# Adafruit_STEMMA_Soil_Sensor.net
KiCad netlist of a schematic drawn in EAGLE
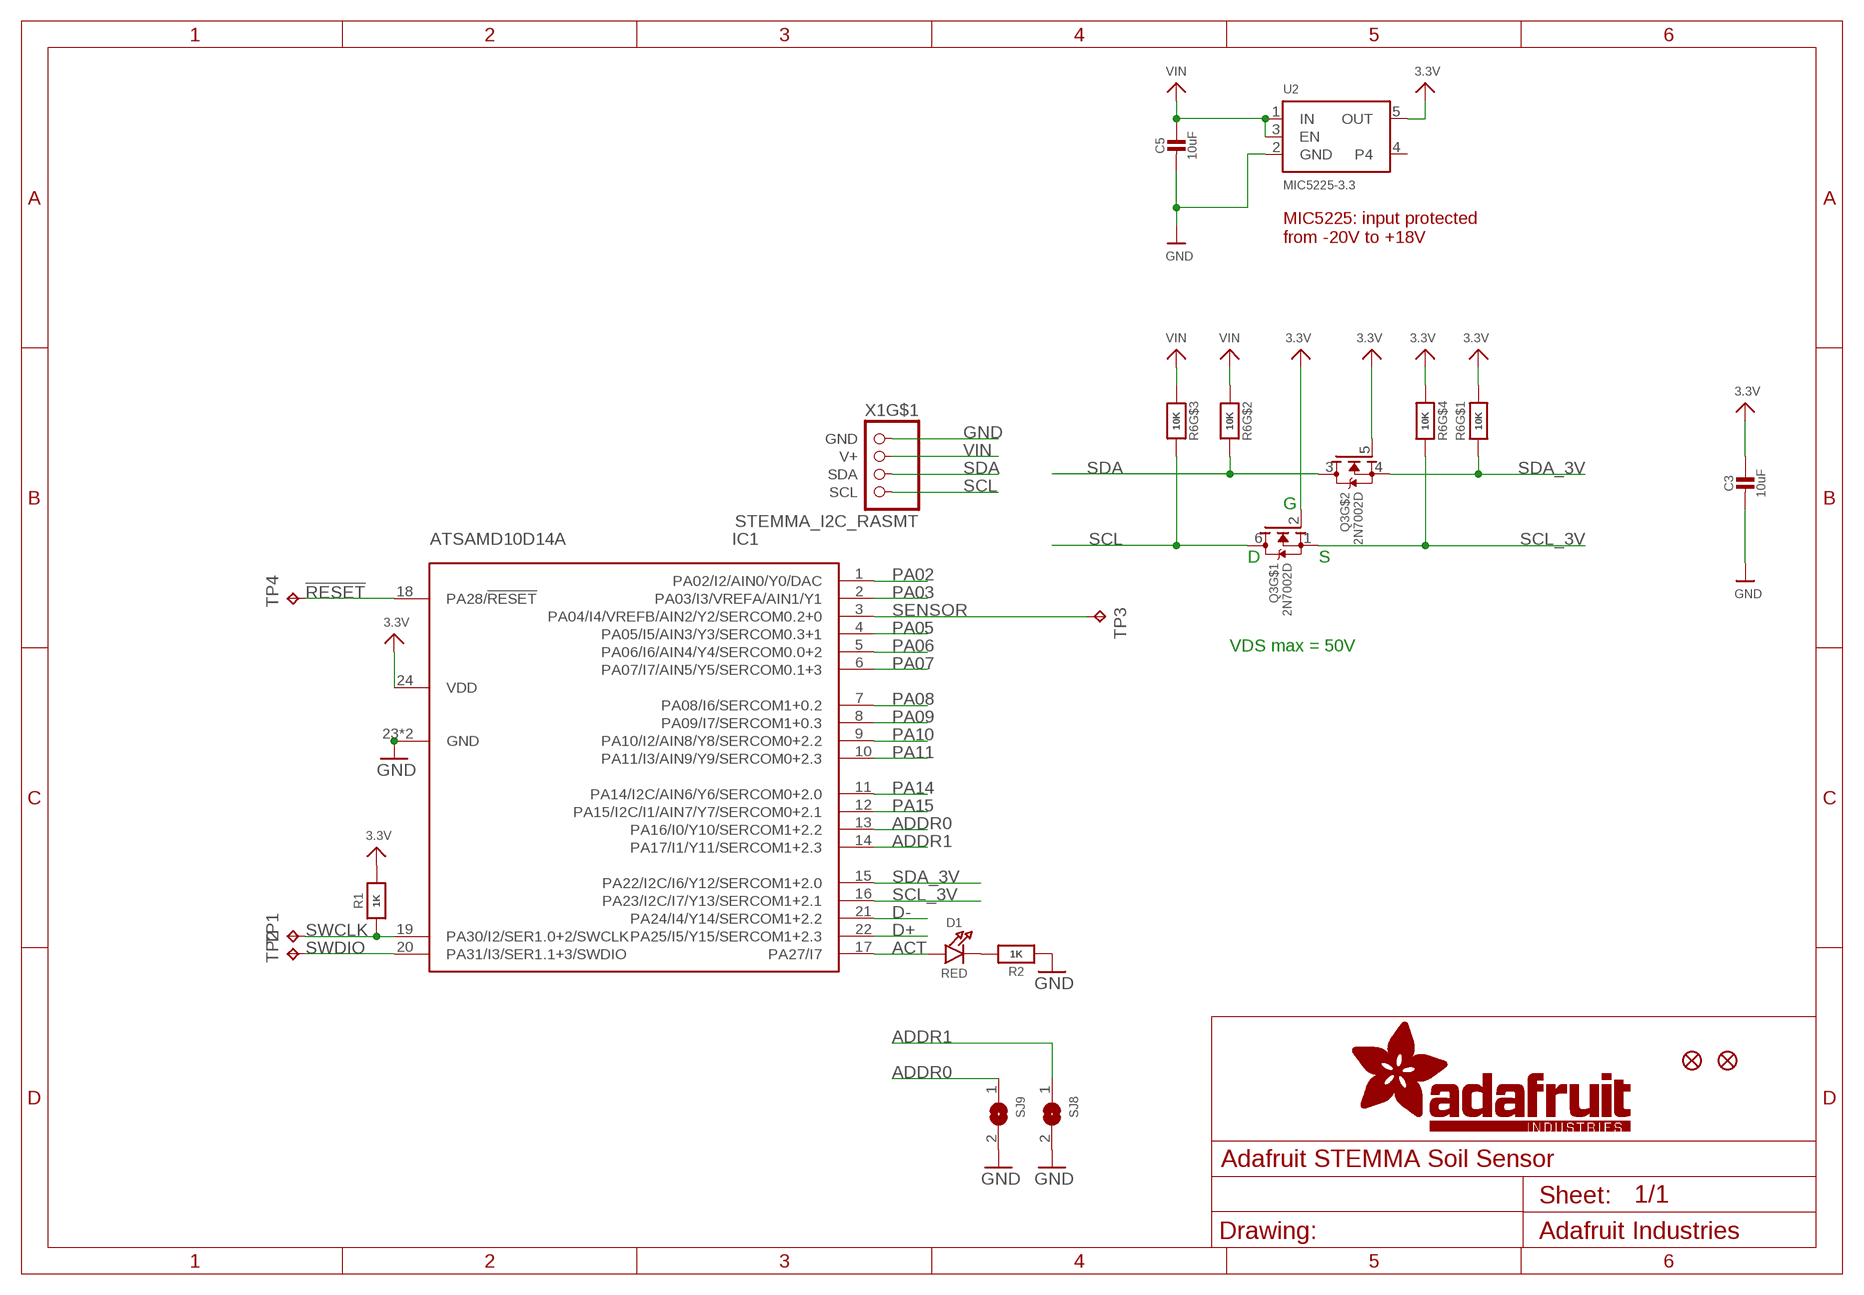
[diagram p0: schematic, sheet 1]

(export (version "E")
  (design (tool "Eeschema 10.0.6"))
  (components
    (comp (ref "C3")
      (value "10uF")
      (footprint "eagle-import:0805-NO")
      (libsource (lib "eagle-import") (part "CAP_CERAMIC0805-NOOUTLINE"))
    )
    (comp (ref "C5")
      (value "10uF")
      (footprint "eagle-import:0805-NO")
      (libsource (lib "eagle-import") (part "CAP_CERAMIC0805-NOOUTLINE"))
    )
    (comp (ref "D1")
      (value "RED")
      (footprint "eagle-import:CHIPLED_0805_NOOUTLINE")
      (libsource (lib "eagle-import") (part "LED0805_NOOUTLINE"))
    )
    (comp (ref "FID1")
      (value "FIDUCIAL_1MM")
      (footprint "eagle-import:FIDUCIAL_1MM")
      (libsource (lib "eagle-import") (part "FIDUCIAL_1MM"))
    )
    (comp (ref "FID2")
      (value "FIDUCIAL_1MM")
      (footprint "eagle-import:FIDUCIAL_1MM")
      (libsource (lib "eagle-import") (part "FIDUCIAL_1MM"))
    )
    (comp (ref "IC1")
      (value "ATSAMD10D14A")
      (footprint "eagle-import:QFN24_4MM")
      (libsource (lib "eagle-import") (part "ATSAMD10D14A"))
    )
    (comp (ref "Q3")
      (value "2N7002D")
      (footprint "eagle-import:SOT363")
      (libsource (lib "eagle-import") (part "MOSFET-N_DUAL"))
    )
    (comp (ref "R1")
      (value "1K")
      (footprint "eagle-import:0603-NO")
      (libsource (lib "eagle-import") (part "RESISTOR_0603_NOOUT"))
    )
    (comp (ref "R2")
      (value "1K")
      (footprint "eagle-import:0603-NO")
      (libsource (lib "eagle-import") (part "RESISTOR_0603_NOOUT"))
    )
    (comp (ref "R6")
      (value "10K")
      (footprint "eagle-import:RESPACK_4X0603")
      (libsource (lib "eagle-import") (part "RESISTOR_4PACK"))
    )
    (comp (ref "SJ8")
      (value "SOLDERJUMPER")
      (footprint "eagle-import:SOLDERJUMPER_ARROW_NOPASTE")
      (libsource (lib "eagle-import") (part "SOLDERJUMPER"))
    )
    (comp (ref "SJ9")
      (value "SOLDERJUMPER")
      (footprint "eagle-import:SOLDERJUMPER_ARROW_NOPASTE")
      (libsource (lib "eagle-import") (part "SOLDERJUMPER"))
    )
    (comp (ref "TP1")
      (value "TPTP15R")
      (footprint "eagle-import:TP15R")
      (libsource (lib "eagle-import") (part "TPTP15R"))
    )
    (comp (ref "TP2")
      (value "TPTP15R")
      (footprint "eagle-import:TP15R")
      (libsource (lib "eagle-import") (part "TPTP15R"))
    )
    (comp (ref "TP3")
      (value "TPTP10R")
      (footprint "eagle-import:TP10R")
      (libsource (lib "eagle-import") (part "TPTP10R"))
    )
    (comp (ref "TP4")
      (value "TPTP15R")
      (footprint "eagle-import:TP15R")
      (libsource (lib "eagle-import") (part "TPTP15R"))
    )
    (comp (ref "U2")
      (value "MIC5225-3.3")
      (footprint "eagle-import:SOT23-5")
      (libsource (lib "eagle-import") (part "VREG_SOT23-5"))
    )
    (comp (ref "X1")
      (value "STEMMA_I2C_RASMT")
      (footprint "eagle-import:JSTPH4")
      (libsource (lib "eagle-import") (part "STEMMA_I2C_RASMT"))
    )
  )
  (nets
    (net (code "1") (name "/ACT") (class "Default")
      (node (ref "D1") (pin "A") (pinfunction "A_A") (pintype "passive"))
      (node (ref "IC1") (pin "17") (pinfunction "PA27/I7_17") (pintype "bidirectional"))
    )
    (net (code "2") (name "/ADDR0") (class "Default")
      (node (ref "IC1") (pin "13") (pinfunction "PA16/I0/Y10/SERCOM1+2.2_13") (pintype "bidirectional"))
      (node (ref "SJ9") (pin "1") (pinfunction "1_1") (pintype "passive"))
    )
    (net (code "3") (name "/ADDR1") (class "Default")
      (node (ref "IC1") (pin "14") (pinfunction "PA17/I1/Y11/SERCOM1+2.3_14") (pintype "bidirectional"))
      (node (ref "SJ8") (pin "1") (pinfunction "1_1") (pintype "passive"))
    )
    (net (code "4") (name "/D+") (class "Default")
      (node (ref "IC1") (pin "22") (pinfunction "PA25/I5/Y15/SERCOM1+2.3_22") (pintype "bidirectional"))
    )
    (net (code "5") (name "/D-") (class "Default")
      (node (ref "IC1") (pin "21") (pinfunction "PA24/I4/Y14/SERCOM1+2.2_21") (pintype "bidirectional"))
    )
    (net (code "6") (name "/PA02") (class "Default")
      (node (ref "IC1") (pin "1") (pinfunction "PA02/I2/AIN0/Y0/DAC_1") (pintype "bidirectional"))
    )
    (net (code "7") (name "/PA03") (class "Default")
      (node (ref "IC1") (pin "2") (pinfunction "PA03/I3/VREFA/AIN1/Y1_2") (pintype "bidirectional"))
    )
    (net (code "8") (name "/PA05") (class "Default")
      (node (ref "IC1") (pin "4") (pinfunction "PA05/I5/AIN3/Y3/SERCOM0.3+1_4") (pintype "bidirectional"))
    )
    (net (code "9") (name "/PA06") (class "Default")
      (node (ref "IC1") (pin "5") (pinfunction "PA06/I6/AIN4/Y4/SERCOM0.0+2_5") (pintype "bidirectional"))
    )
    (net (code "10") (name "/PA07") (class "Default")
      (node (ref "IC1") (pin "6") (pinfunction "PA07/I7/AIN5/Y5/SERCOM0.1+3_6") (pintype "bidirectional"))
    )
    (net (code "11") (name "/PA08") (class "Default")
      (node (ref "IC1") (pin "7") (pinfunction "PA08/I6/SERCOM1+0.2_7") (pintype "bidirectional"))
    )
    (net (code "12") (name "/PA09") (class "Default")
      (node (ref "IC1") (pin "8") (pinfunction "PA09/I7/SERCOM1+0.3_8") (pintype "bidirectional"))
    )
    (net (code "13") (name "/PA10") (class "Default")
      (node (ref "IC1") (pin "9") (pinfunction "PA10/I2/AIN8/Y8/SERCOM0+2.2_9") (pintype "bidirectional"))
    )
    (net (code "14") (name "/PA11") (class "Default")
      (node (ref "IC1") (pin "10") (pinfunction "PA11/I3/AIN9/Y9/SERCOM0+2.3_10") (pintype "bidirectional"))
    )
    (net (code "15") (name "/PA14") (class "Default")
      (node (ref "IC1") (pin "11") (pinfunction "PA14/I2C/AIN6/Y6/SERCOM0+2.0_11") (pintype "bidirectional"))
    )
    (net (code "16") (name "/PA15") (class "Default")
      (node (ref "IC1") (pin "12") (pinfunction "PA15/I2C/I1/AIN7/Y7/SERCOM0+2.1_12") (pintype "bidirectional"))
    )
    (net (code "17") (name "/SCL") (class "Default")
      (node (ref "Q3") (pin "6") (pinfunction "D_6") (pintype "bidirectional"))
      (node (ref "R6") (pin "6") (pinfunction "2_6") (pintype "passive"))
      (node (ref "X1") (pin "4") (pinfunction "SCL_4") (pintype "passive"))
    )
    (net (code "18") (name "/SCL_3V") (class "Default")
      (node (ref "IC1") (pin "16") (pinfunction "PA23/I2C/I7/Y13/SERCOM1+2.1_16") (pintype "bidirectional"))
      (node (ref "Q3") (pin "1") (pinfunction "S_1") (pintype "bidirectional"))
      (node (ref "R6") (pin "4") (pinfunction "1_4") (pintype "passive"))
    )
    (net (code "19") (name "/SDA") (class "Default")
      (node (ref "Q3") (pin "3") (pinfunction "D_3") (pintype "bidirectional"))
      (node (ref "R6") (pin "7") (pinfunction "2_7") (pintype "passive"))
      (node (ref "X1") (pin "3") (pinfunction "SDA_3") (pintype "passive"))
    )
    (net (code "20") (name "/SDA_3V") (class "Default")
      (node (ref "IC1") (pin "15") (pinfunction "PA22/I2C/I6/Y12/SERCOM1+2.0_15") (pintype "bidirectional"))
      (node (ref "Q3") (pin "4") (pinfunction "S_4") (pintype "bidirectional"))
      (node (ref "R6") (pin "8") (pinfunction "2_8") (pintype "passive"))
    )
    (net (code "21") (name "/SENSOR") (class "Default")
      (node (ref "IC1") (pin "3") (pinfunction "PA04/I4/VREFB/AIN2/Y2/SERCOM0.2+0_3") (pintype "bidirectional"))
      (node (ref "TP3") (pin "TP") (pinfunction "TP_TP") (pintype "input"))
    )
    (net (code "22") (name "/SWCLK") (class "Default")
      (node (ref "IC1") (pin "19") (pinfunction "PA30/I2/SER1.0+2/SWCLK_19") (pintype "bidirectional"))
      (node (ref "R1") (pin "1") (pinfunction "1_1") (pintype "passive"))
      (node (ref "TP1") (pin "TP") (pinfunction "TP_TP") (pintype "input"))
    )
    (net (code "23") (name "/SWDIO") (class "Default")
      (node (ref "IC1") (pin "20") (pinfunction "PA31/I3/SER1.1+3/SWDIO_20") (pintype "bidirectional"))
      (node (ref "TP2") (pin "TP") (pinfunction "TP_TP") (pintype "input"))
    )
    (net (code "24") (name "/~{RESET}") (class "Default")
      (node (ref "IC1") (pin "18") (pinfunction "PA28/~{RESET}_18") (pintype "bidirectional"))
      (node (ref "TP4") (pin "TP") (pinfunction "TP_TP") (pintype "input"))
    )
    (net (code "25") (name "3.3V") (class "Default")
      (node (ref "C3") (pin "1") (pinfunction "1_1") (pintype "passive"))
      (node (ref "IC1") (pin "24") (pinfunction "VDD_24") (pintype "power_in"))
      (node (ref "Q3") (pin "2") (pinfunction "G_2") (pintype "bidirectional"))
      (node (ref "Q3") (pin "5") (pinfunction "G_5") (pintype "bidirectional"))
      (node (ref "R1") (pin "2") (pinfunction "2_2") (pintype "passive"))
      (node (ref "R6") (pin "1") (pinfunction "1_1") (pintype "passive"))
      (node (ref "R6") (pin "5") (pinfunction "2_5") (pintype "passive"))
      (node (ref "U2") (pin "5") (pinfunction "OUT_5") (pintype "power_in"))
    )
    (net (code "26") (name "GND") (class "Default")
      (node (ref "C3") (pin "2") (pinfunction "2_2") (pintype "passive"))
      (node (ref "C5") (pin "2") (pinfunction "2_2") (pintype "passive"))
      (node (ref "IC1") (pin "23") (pinfunction "GND_23") (pintype "power_in"))
      (node (ref "IC1") (pin "THERM") (pinfunction "GND_THERM") (pintype "power_in"))
      (node (ref "R2") (pin "1") (pinfunction "1_1") (pintype "passive"))
      (node (ref "SJ8") (pin "2") (pinfunction "2_2") (pintype "passive"))
      (node (ref "SJ9") (pin "2") (pinfunction "2_2") (pintype "passive"))
      (node (ref "U2") (pin "2") (pinfunction "GND_2") (pintype "power_in"))
      (node (ref "X1") (pin "1") (pinfunction "GND_1") (pintype "passive"))
    )
    (net (code "27") (name "Net-(D1-PadC)") (class "Default")
      (node (ref "D1") (pin "C") (pinfunction "C_C") (pintype "passive"))
      (node (ref "R2") (pin "2") (pinfunction "2_2") (pintype "passive"))
    )
    (net (code "28") (name "VIN") (class "Default")
      (node (ref "C5") (pin "1") (pinfunction "1_1") (pintype "passive"))
      (node (ref "R6") (pin "2") (pinfunction "1_2") (pintype "passive"))
      (node (ref "R6") (pin "3") (pinfunction "1_3") (pintype "passive"))
      (node (ref "U2") (pin "1") (pinfunction "IN_1") (pintype "power_in"))
      (node (ref "U2") (pin "3") (pinfunction "EN_3") (pintype "input"))
      (node (ref "X1") (pin "2") (pinfunction "V+_2") (pintype "passive"))
    )
    (net (code "29") (name "unconnected-(U2-P4-Pad4)") (class "Default")
      (node (ref "U2") (pin "4") (pinfunction "P4_4") (pintype "bidirectional"))
    )
  )
)
